# Microcontroller.net
KiCad netlist of a schematic drawn in Altium Designer
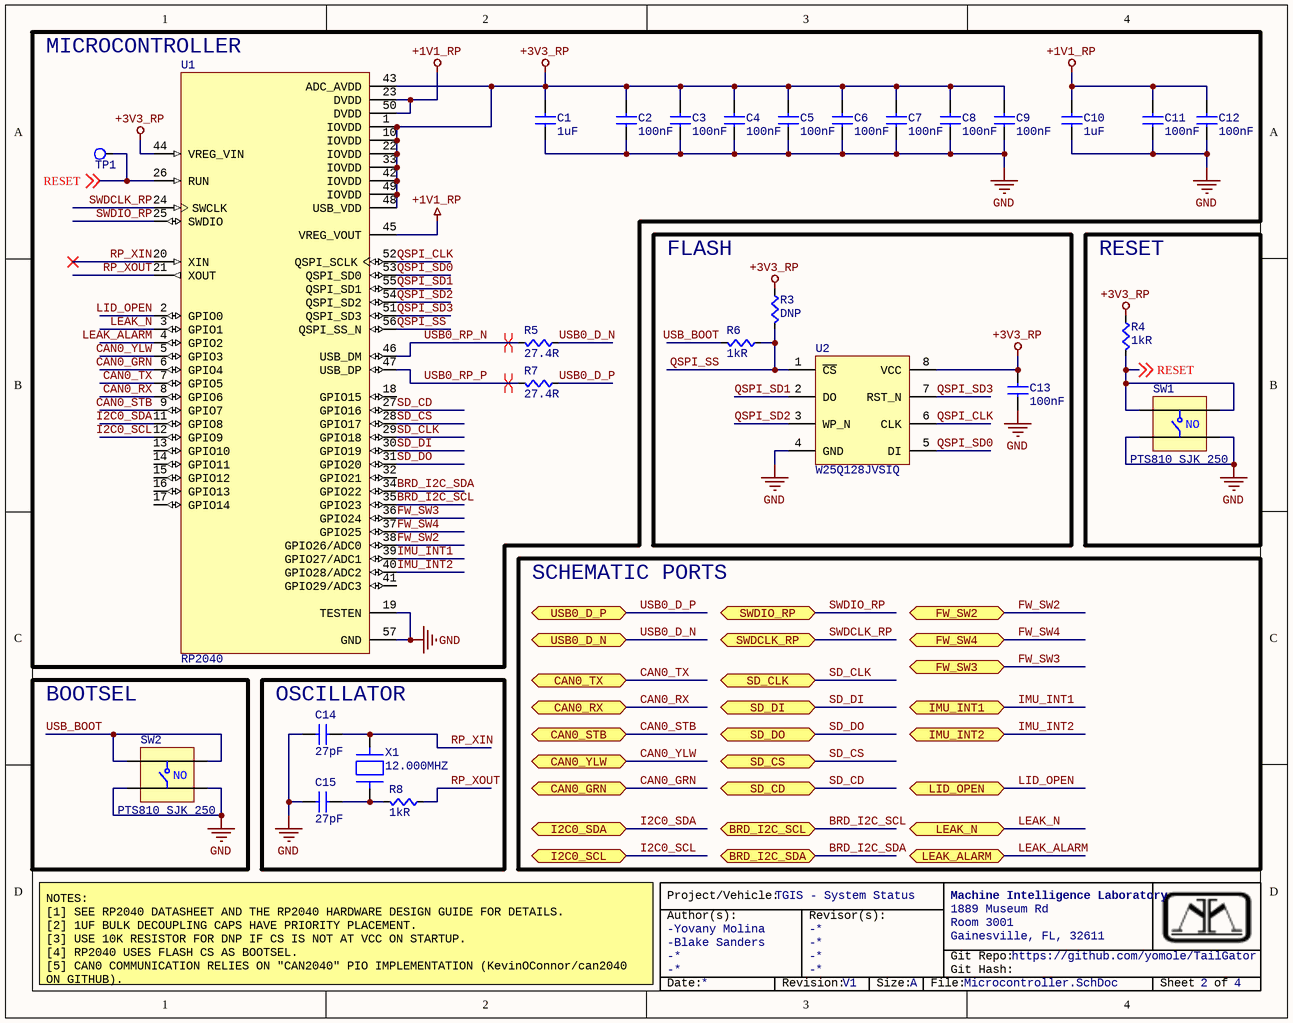
[diagram p0: Microcontroller.SchDoc]

(export (version "E")
  (design (tool "Eeschema 10.0.6"))
  (components
    (comp (ref "C1")
      (value "1uF")
      (footprint "CAPC0603")
      (description "Ceramic Capacitor, Multilayer, Cera")
      (fields (field (name "PART NUMBER") "CC0603KRX7R7BB105") (field (name "MANUFACTURER") "Yageo"))
      (libsource (lib "Parts") (part "NP_Capacitor"))
    )
    (comp (ref "C2")
      (value "100nF")
      (footprint "CAPC0603")
      (description "Ceramic Capacitor, Multilayer, Cera")
      (fields (field (name "PART NUMBER") "CC0603KRX7R7BB104") (field (name "MANUFACTURER") "Yageo"))
      (libsource (lib "Parts") (part "NP_Capacitor"))
    )
    (comp (ref "C3")
      (value "100nF")
      (footprint "CAPC0603")
      (description "Ceramic Capacitor, Multilayer, Cera")
      (fields (field (name "PART NUMBER") "CC0603KRX7R7BB104") (field (name "MANUFACTURER") "Yageo"))
      (libsource (lib "Parts") (part "NP_Capacitor"))
    )
    (comp (ref "C4")
      (value "100nF")
      (footprint "CAPC0603")
      (description "Ceramic Capacitor, Multilayer, Cera")
      (fields (field (name "PART NUMBER") "CC0603KRX7R7BB104") (field (name "MANUFACTURER") "Yageo"))
      (libsource (lib "Parts") (part "NP_Capacitor"))
    )
    (comp (ref "C5")
      (value "100nF")
      (footprint "CAPC0603")
      (description "Ceramic Capacitor, Multilayer, Cera")
      (fields (field (name "PART NUMBER") "CC0603KRX7R7BB104") (field (name "MANUFACTURER") "Yageo"))
      (libsource (lib "Parts") (part "NP_Capacitor"))
    )
    (comp (ref "C6")
      (value "100nF")
      (footprint "CAPC0603")
      (description "Ceramic Capacitor, Multilayer, Cera")
      (fields (field (name "PART NUMBER") "CC0603KRX7R7BB104") (field (name "MANUFACTURER") "Yageo"))
      (libsource (lib "Parts") (part "NP_Capacitor"))
    )
    (comp (ref "C7")
      (value "100nF")
      (footprint "CAPC0603")
      (description "Ceramic Capacitor, Multilayer, Cera")
      (fields (field (name "PART NUMBER") "CC0603KRX7R7BB104") (field (name "MANUFACTURER") "Yageo"))
      (libsource (lib "Parts") (part "NP_Capacitor"))
    )
    (comp (ref "C8")
      (value "100nF")
      (footprint "CAPC0603")
      (description "Ceramic Capacitor, Multilayer, Cera")
      (fields (field (name "PART NUMBER") "CC0603KRX7R7BB104") (field (name "MANUFACTURER") "Yageo"))
      (libsource (lib "Parts") (part "NP_Capacitor"))
    )
    (comp (ref "C9")
      (value "100nF")
      (footprint "CAPC0603")
      (description "Ceramic Capacitor, Multilayer, Cera")
      (fields (field (name "PART NUMBER") "CC0603KRX7R7BB104") (field (name "MANUFACTURER") "Yageo"))
      (libsource (lib "Parts") (part "NP_Capacitor"))
    )
    (comp (ref "C10")
      (value "1uF")
      (footprint "CAPC0603")
      (description "Ceramic Capacitor, Multilayer, Cera")
      (fields (field (name "PART NUMBER") "CC0603KRX7R7BB105") (field (name "MANUFACTURER") "Yageo"))
      (libsource (lib "Parts") (part "NP_Capacitor"))
    )
    (comp (ref "C11")
      (value "100nF")
      (footprint "CAPC0603")
      (description "Ceramic Capacitor, Multilayer, Cera")
      (fields (field (name "PART NUMBER") "CC0603KRX7R7BB104") (field (name "MANUFACTURER") "Yageo"))
      (libsource (lib "Parts") (part "NP_Capacitor"))
    )
    (comp (ref "C12")
      (value "100nF")
      (footprint "CAPC0603")
      (description "Ceramic Capacitor, Multilayer, Cera")
      (fields (field (name "PART NUMBER") "CC0603KRX7R7BB104") (field (name "MANUFACTURER") "Yageo"))
      (libsource (lib "Parts") (part "NP_Capacitor"))
    )
    (comp (ref "C13")
      (value "100nF")
      (footprint "CAPC0603")
      (description "Ceramic Capacitor, Multilayer, Cera")
      (fields (field (name "PART NUMBER") "CC0603KRX7R7BB104") (field (name "MANUFACTURER") "Yageo"))
      (libsource (lib "Parts") (part "NP_Capacitor"))
    )
    (comp (ref "C14")
      (value "27pF")
      (footprint "CAPC0603")
      (description "Ceramic Capacitor, Multilayer, Cera")
      (fields (field (name "PART NUMBER") "CC0603JRNPO9BN270") (field (name "MANUFACTURER") "Yageo"))
      (libsource (lib "Parts") (part "NP_Capacitor"))
    )
    (comp (ref "C15")
      (value "27pF")
      (footprint "CAPC0603")
      (description "Ceramic Capacitor, Multilayer, Cera")
      (fields (field (name "PART NUMBER") "CC0603JRNPO9BN270") (field (name "MANUFACTURER") "Yageo"))
      (libsource (lib "Parts") (part "NP_Capacitor"))
    )
    (comp (ref "R3")
      (value "DNP")
      (footprint "RES0603")
      (fields (field (name "Comment") "Res"))
      (libsource (lib "Passives") (part "Res"))
    )
    (comp (ref "R4")
      (value "1kR")
      (footprint "RES0603")
      (description "Fixed Resistor, Metal Glaze/thick F")
      (fields (field (name "PART NUMBER") "RC0603FR-071KL") (field (name "POWER") "100mW"))
      (libsource (lib "Parts") (part "Resistor"))
    )
    (comp (ref "R5")
      (value "27.4R")
      (footprint "RES0603")
      (description "Fixed Resistor, Metal Glaze/thick F")
      (fields (field (name "PART NUMBER") "RC0603FR-0727R4L") (field (name "POWER") "100mW"))
      (libsource (lib "Parts") (part "Resistor"))
    )
    (comp (ref "R6")
      (value "1kR")
      (footprint "RES0603")
      (description "Fixed Resistor, Metal Glaze/thick F")
      (fields (field (name "PART NUMBER") "RC0603FR-071KL") (field (name "POWER") "100mW"))
      (libsource (lib "Parts") (part "Resistor"))
    )
    (comp (ref "R7")
      (value "27.4R")
      (footprint "RES0603")
      (description "Fixed Resistor, Metal Glaze/thick F")
      (fields (field (name "PART NUMBER") "RC0603FR-0727R4L") (field (name "POWER") "100mW"))
      (libsource (lib "Parts") (part "Resistor"))
    )
    (comp (ref "R8")
      (value "1kR")
      (footprint "RES0603")
      (description "Fixed Resistor, Metal Glaze/thick F")
      (fields (field (name "PART NUMBER") "RC0603FR-071KL") (field (name "POWER") "100mW"))
      (libsource (lib "Parts") (part "Resistor"))
    )
    (comp (ref "SW1")
      (value "PTS810 SJK 250")
      (footprint "SW_PTS810_SJM_250_SMTR_LFS")
      (description "Tactile Switch SPST-NO Top Actuated Surface Mount")
      (libsource (lib "TGIS_Microcontrollers") (part "PTS810 SJK 250 SMTR LFS"))
    )
    (comp (ref "SW2")
      (value "PTS810 SJK 250")
      (footprint "SW_PTS810_SJM_250_SMTR_LFS")
      (description "Tactile Switch SPST-NO Top Actuated Surface Mount")
      (libsource (lib "TGIS_Microcontrollers") (part "PTS810 SJK 250 SMTR LFS"))
    )
    (comp (ref "TP1") (value "TP") (footprint "TPAD-60MIL") (libsource (lib "TGIS") (part "TP")))
    (comp (ref "U1")
      (value "RP2040")
      (footprint "QFN40P700X700X90-57N")
      (description "ARM® Cortex®-M0+ - Microcontroller IC 32-Bit Dual-Core 133MHz External Program Memory 56-QFN (7x7)")
      (fields (field (name "MF") "Raspberry Pi") (field (name "MP") "SC0914(13)"))
      (libsource (lib "TGIS_Microcontrollers") (part "SC0914(13)"))
    )
    (comp (ref "U2")
      (value "W25Q128JVSIQ")
      (footprint "SOIC127P790X216-8N")
      (description "FLASH - NOR Memory IC 128Mbit SPI - Quad I/O, QPI, DTR 133 MHz 8-SOIC")
      (libsource (lib "TGIS_Microcontrollers") (part "W25Q128JVSIQ"))
    )
    (comp (ref "X1")
      (value "12.000MHZ")
      (footprint "ABLS-12.000MHZ")
      (description "12 MHz ±20ppm Crystal 18pF 50 Ohms HC-49/US")
      (libsource (lib "TGIS_Microcontrollers") (part "ABLS-12.000MHZ"))
    )
  )
  (nets
    (net (code "1") (name "+1V1_RP") (class "Default")
      (node (ref "C10") (pin "2") (pinfunction "B_2") (pintype "passive"))
      (node (ref "C11") (pin "2") (pinfunction "B_2") (pintype "passive"))
      (node (ref "C12") (pin "2") (pinfunction "B_2") (pintype "passive"))
      (node (ref "U1") (pin "23") (pinfunction "DVDD_23") (pintype "power_in"))
      (node (ref "U1") (pin "45") (pinfunction "VREG_VOUT_45") (pintype "power_in"))
      (node (ref "U1") (pin "50") (pinfunction "DVDD_50") (pintype "power_in"))
    )
    (net (code "2") (name "+3V3_RP") (class "Default")
      (node (ref "C1") (pin "2") (pinfunction "B_2") (pintype "passive"))
      (node (ref "C13") (pin "2") (pinfunction "B_2") (pintype "passive"))
      (node (ref "C2") (pin "2") (pinfunction "B_2") (pintype "passive"))
      (node (ref "C3") (pin "2") (pinfunction "B_2") (pintype "passive"))
      (node (ref "C4") (pin "2") (pinfunction "B_2") (pintype "passive"))
      (node (ref "C5") (pin "2") (pinfunction "B_2") (pintype "passive"))
      (node (ref "C6") (pin "2") (pinfunction "B_2") (pintype "passive"))
      (node (ref "C7") (pin "2") (pinfunction "B_2") (pintype "passive"))
      (node (ref "C8") (pin "2") (pinfunction "B_2") (pintype "passive"))
      (node (ref "C9") (pin "2") (pinfunction "B_2") (pintype "passive"))
      (node (ref "R3") (pin "2") (pinfunction "B_2") (pintype "passive"))
      (node (ref "R4") (pin "2") (pinfunction "B_2") (pintype "passive"))
      (node (ref "U1") (pin "1") (pinfunction "IOVDD_1") (pintype "power_in"))
      (node (ref "U1") (pin "10") (pinfunction "IOVDD_10") (pintype "power_in"))
      (node (ref "U1") (pin "22") (pinfunction "IOVDD_22") (pintype "power_in"))
      (node (ref "U1") (pin "33") (pinfunction "IOVDD_33") (pintype "power_in"))
      (node (ref "U1") (pin "42") (pinfunction "IOVDD_42") (pintype "power_in"))
      (node (ref "U1") (pin "43") (pinfunction "ADC_AVDD_43") (pintype "power_in"))
      (node (ref "U1") (pin "44") (pinfunction "VREG_VIN_44") (pintype "input"))
      (node (ref "U1") (pin "48") (pinfunction "USB_VDD_48") (pintype "power_in"))
      (node (ref "U1") (pin "49") (pinfunction "IOVDD_49") (pintype "power_in"))
      (node (ref "U2") (pin "8") (pinfunction "VCC_8") (pintype "passive"))
    )
    (net (code "3") (name "/BRD_I2C_SCL") (class "Default")
      (node (ref "U1") (pin "35") (pinfunction "GPIO23_35") (pintype "bidirectional"))
    )
    (net (code "4") (name "/BRD_I2C_SDA") (class "Default")
      (node (ref "U1") (pin "34") (pinfunction "GPIO22_34") (pintype "bidirectional"))
    )
    (net (code "5") (name "/CAN0_GRN") (class "Default")
      (node (ref "U1") (pin "6") (pinfunction "GPIO4_6") (pintype "bidirectional"))
    )
    (net (code "6") (name "/CAN0_RX") (class "Default")
      (node (ref "U1") (pin "8") (pinfunction "GPIO6_8") (pintype "bidirectional"))
    )
    (net (code "7") (name "/CAN0_STB") (class "Default")
      (node (ref "U1") (pin "9") (pinfunction "GPIO7_9") (pintype "bidirectional"))
    )
    (net (code "8") (name "/CAN0_TX") (class "Default")
      (node (ref "U1") (pin "7") (pinfunction "GPIO5_7") (pintype "bidirectional"))
    )
    (net (code "9") (name "/CAN0_YLW") (class "Default")
      (node (ref "U1") (pin "5") (pinfunction "GPIO3_5") (pintype "bidirectional"))
    )
    (net (code "10") (name "/FW_SW2") (class "Default")
      (node (ref "U1") (pin "38") (pinfunction "GPIO26/ADC0_38") (pintype "bidirectional"))
    )
    (net (code "11") (name "/FW_SW3") (class "Default")
      (node (ref "U1") (pin "36") (pinfunction "GPIO24_36") (pintype "bidirectional"))
    )
    (net (code "12") (name "/FW_SW4") (class "Default")
      (node (ref "U1") (pin "37") (pinfunction "GPIO25_37") (pintype "bidirectional"))
    )
    (net (code "13") (name "/I2C0_SCL") (class "Default")
      (node (ref "U1") (pin "12") (pinfunction "GPIO9_12") (pintype "bidirectional"))
    )
    (net (code "14") (name "/I2C0_SDA") (class "Default")
      (node (ref "U1") (pin "11") (pinfunction "GPIO8_11") (pintype "bidirectional"))
    )
    (net (code "15") (name "/IMU_INT1") (class "Default")
      (node (ref "U1") (pin "39") (pinfunction "GPIO27/ADC1_39") (pintype "bidirectional"))
    )
    (net (code "16") (name "/IMU_INT2") (class "Default")
      (node (ref "U1") (pin "40") (pinfunction "GPIO28/ADC2_40") (pintype "bidirectional"))
    )
    (net (code "17") (name "/LEAK_ALARM") (class "Default")
      (node (ref "U1") (pin "4") (pinfunction "GPIO2_4") (pintype "bidirectional"))
    )
    (net (code "18") (name "/LEAK_N") (class "Default")
      (node (ref "U1") (pin "3") (pinfunction "GPIO1_3") (pintype "bidirectional"))
    )
    (net (code "19") (name "/LID_OPEN") (class "Default")
      (node (ref "U1") (pin "2") (pinfunction "GPIO0_2") (pintype "bidirectional"))
    )
    (net (code "20") (name "/QSPI_CLK") (class "Default")
      (node (ref "U1") (pin "52") (pinfunction "QSPI_SCLK_52") (pintype "bidirectional"))
      (node (ref "U2") (pin "6") (pinfunction "CLK_6") (pintype "passive"))
    )
    (net (code "21") (name "/QSPI_SD0") (class "Default")
      (node (ref "U1") (pin "53") (pinfunction "QSPI_SD0_53") (pintype "bidirectional"))
      (node (ref "U2") (pin "5") (pinfunction "DI_5") (pintype "passive"))
    )
    (net (code "22") (name "/QSPI_SD1") (class "Default")
      (node (ref "U1") (pin "55") (pinfunction "QSPI_SD1_55") (pintype "bidirectional"))
      (node (ref "U2") (pin "2") (pinfunction "DO_2") (pintype "passive"))
    )
    (net (code "23") (name "/QSPI_SD2") (class "Default")
      (node (ref "U1") (pin "54") (pinfunction "QSPI_SD2_54") (pintype "bidirectional"))
      (node (ref "U2") (pin "3") (pinfunction "WP_N_3") (pintype "passive"))
    )
    (net (code "24") (name "/QSPI_SD3") (class "Default")
      (node (ref "U1") (pin "51") (pinfunction "QSPI_SD3_51") (pintype "bidirectional"))
      (node (ref "U2") (pin "7") (pinfunction "RST_N_7") (pintype "passive"))
    )
    (net (code "25") (name "/QSPI_SS") (class "Default")
      (node (ref "R3") (pin "1") (pinfunction "A_1") (pintype "passive"))
      (node (ref "R6") (pin "2") (pinfunction "B_2") (pintype "passive"))
      (node (ref "U1") (pin "56") (pinfunction "QSPI_SS_N_56") (pintype "bidirectional"))
      (node (ref "U2") (pin "1") (pinfunction "CS_1") (pintype "passive"))
    )
    (net (code "26") (name "/RP_XIN") (class "Default")
      (node (ref "C14") (pin "2") (pinfunction "B_2") (pintype "passive"))
      (node (ref "U1") (pin "20") (pinfunction "XIN_20") (pintype "input"))
      (node (ref "X1") (pin "2") (pinfunction "2_2") (pintype "passive"))
    )
    (net (code "27") (name "/RP_XOUT") (class "Default")
      (node (ref "R8") (pin "2") (pinfunction "B_2") (pintype "passive"))
      (node (ref "U1") (pin "21") (pinfunction "XOUT_21") (pintype "output"))
    )
    (net (code "28") (name "/SD_CD") (class "Default")
      (node (ref "U1") (pin "27") (pinfunction "GPIO16_27") (pintype "bidirectional"))
    )
    (net (code "29") (name "/SD_CLK") (class "Default")
      (node (ref "U1") (pin "29") (pinfunction "GPIO18_29") (pintype "bidirectional"))
    )
    (net (code "30") (name "/SD_CS") (class "Default")
      (node (ref "U1") (pin "28") (pinfunction "GPIO17_28") (pintype "bidirectional"))
    )
    (net (code "31") (name "/SD_DI") (class "Default")
      (node (ref "U1") (pin "30") (pinfunction "GPIO19_30") (pintype "bidirectional"))
    )
    (net (code "32") (name "/SD_DO") (class "Default")
      (node (ref "U1") (pin "31") (pinfunction "GPIO20_31") (pintype "bidirectional"))
    )
    (net (code "33") (name "/SWDCLK_RP") (class "Default")
      (node (ref "U1") (pin "24") (pinfunction "SWCLK_24") (pintype "input"))
    )
    (net (code "34") (name "/SWDIO_RP") (class "Default")
      (node (ref "U1") (pin "25") (pinfunction "SWDIO_25") (pintype "bidirectional"))
    )
    (net (code "35") (name "/USB0_D_N") (class "Default")
      (node (ref "R5") (pin "2") (pinfunction "B_2") (pintype "passive"))
    )
    (net (code "36") (name "/USB0_D_P") (class "Default")
      (node (ref "R7") (pin "2") (pinfunction "B_2") (pintype "passive"))
    )
    (net (code "37") (name "/USB0_RP_N") (class "Default")
      (node (ref "R5") (pin "1") (pinfunction "A_1") (pintype "passive"))
      (node (ref "U1") (pin "46") (pinfunction "USB_DM_46") (pintype "bidirectional"))
    )
    (net (code "38") (name "/USB0_RP_P") (class "Default")
      (node (ref "R7") (pin "1") (pinfunction "A_1") (pintype "passive"))
      (node (ref "U1") (pin "47") (pinfunction "USB_DP_47") (pintype "bidirectional"))
    )
    (net (code "39") (name "/USB_BOOT") (class "Default")
      (node (ref "R6") (pin "1") (pinfunction "A_1") (pintype "passive"))
      (node (ref "SW2") (pin "1") (pinfunction "1_1") (pintype "passive"))
      (node (ref "SW2") (pin "2") (pinfunction "2_2") (pintype "passive"))
    )
    (net (code "40") (name "GND") (class "Default")
      (node (ref "C1") (pin "1") (pinfunction "A_1") (pintype "passive"))
      (node (ref "C10") (pin "1") (pinfunction "A_1") (pintype "passive"))
      (node (ref "C11") (pin "1") (pinfunction "A_1") (pintype "passive"))
      (node (ref "C12") (pin "1") (pinfunction "A_1") (pintype "passive"))
      (node (ref "C13") (pin "1") (pinfunction "A_1") (pintype "passive"))
      (node (ref "C14") (pin "1") (pinfunction "A_1") (pintype "passive"))
      (node (ref "C15") (pin "1") (pinfunction "A_1") (pintype "passive"))
      (node (ref "C2") (pin "1") (pinfunction "A_1") (pintype "passive"))
      (node (ref "C3") (pin "1") (pinfunction "A_1") (pintype "passive"))
      (node (ref "C4") (pin "1") (pinfunction "A_1") (pintype "passive"))
      (node (ref "C5") (pin "1") (pinfunction "A_1") (pintype "passive"))
      (node (ref "C6") (pin "1") (pinfunction "A_1") (pintype "passive"))
      (node (ref "C7") (pin "1") (pinfunction "A_1") (pintype "passive"))
      (node (ref "C8") (pin "1") (pinfunction "A_1") (pintype "passive"))
      (node (ref "C9") (pin "1") (pinfunction "A_1") (pintype "passive"))
      (node (ref "SW1") (pin "3") (pinfunction "3_3") (pintype "passive"))
      (node (ref "SW1") (pin "4") (pinfunction "4_4") (pintype "passive"))
      (node (ref "SW2") (pin "3") (pinfunction "3_3") (pintype "passive"))
      (node (ref "SW2") (pin "4") (pinfunction "4_4") (pintype "passive"))
      (node (ref "U1") (pin "19") (pinfunction "TESTEN_19") (pintype "passive"))
      (node (ref "U1") (pin "57") (pinfunction "GND_57") (pintype "power_in"))
      (node (ref "U2") (pin "4") (pinfunction "GND_4") (pintype "passive"))
    )
    (net (code "41") (name "Net-(C15-B)") (class "Default")
      (node (ref "C15") (pin "2") (pinfunction "B_2") (pintype "passive"))
      (node (ref "R8") (pin "1") (pinfunction "A_1") (pintype "passive"))
      (node (ref "X1") (pin "1") (pinfunction "1_1") (pintype "passive"))
    )
    (net (code "42") (name "RESET") (class "Default")
      (node (ref "R4") (pin "1") (pinfunction "A_1") (pintype "passive"))
      (node (ref "SW1") (pin "1") (pinfunction "1_1") (pintype "passive"))
      (node (ref "SW1") (pin "2") (pinfunction "2_2") (pintype "passive"))
      (node (ref "TP1") (pin "1") (pinfunction "1_1") (pintype "passive"))
      (node (ref "U1") (pin "26") (pinfunction "RUN_26") (pintype "input"))
    )
    (net (code "43") (name "unconnected-(U1-GPIO10-Pad13)") (class "Default")
      (node (ref "U1") (pin "13") (pinfunction "GPIO10_13") (pintype "bidirectional"))
    )
    (net (code "44") (name "unconnected-(U1-GPIO11-Pad14)") (class "Default")
      (node (ref "U1") (pin "14") (pinfunction "GPIO11_14") (pintype "bidirectional"))
    )
    (net (code "45") (name "unconnected-(U1-GPIO12-Pad15)") (class "Default")
      (node (ref "U1") (pin "15") (pinfunction "GPIO12_15") (pintype "bidirectional"))
    )
    (net (code "46") (name "unconnected-(U1-GPIO13-Pad16)") (class "Default")
      (node (ref "U1") (pin "16") (pinfunction "GPIO13_16") (pintype "bidirectional"))
    )
    (net (code "47") (name "unconnected-(U1-GPIO14-Pad17)") (class "Default")
      (node (ref "U1") (pin "17") (pinfunction "GPIO14_17") (pintype "bidirectional"))
    )
    (net (code "48") (name "unconnected-(U1-GPIO15-Pad18)") (class "Default")
      (node (ref "U1") (pin "18") (pinfunction "GPIO15_18") (pintype "bidirectional"))
    )
    (net (code "49") (name "unconnected-(U1-GPIO21-Pad32)") (class "Default")
      (node (ref "U1") (pin "32") (pinfunction "GPIO21_32") (pintype "bidirectional"))
    )
    (net (code "50") (name "unconnected-(U1-GPIO29{slash}ADC3-Pad41)") (class "Default")
      (node (ref "U1") (pin "41") (pinfunction "GPIO29/ADC3_41") (pintype "bidirectional"))
    )
  )
)
